# LED0805-8_Sch.net
KiCad netlist of a schematic drawn in Altium Designer
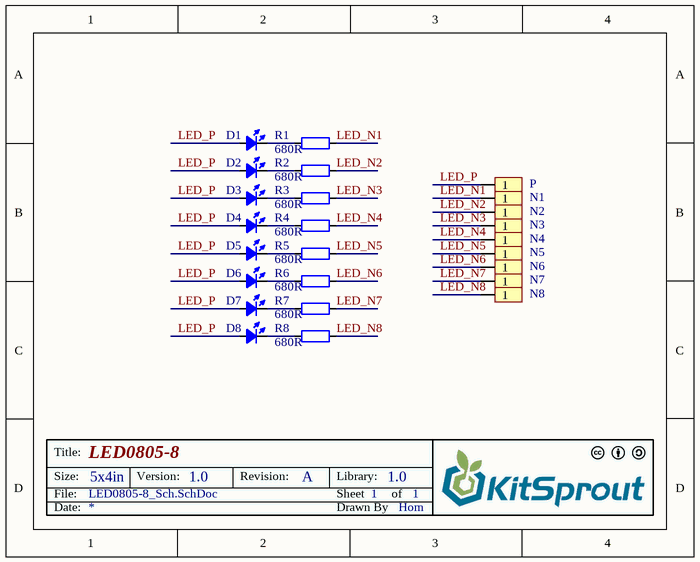
[diagram p0: LED0805-8_Sch.SchDoc]

(export (version "E")
  (design (tool "Eeschema 10.0.6"))
  (components
    (comp (ref "D1")
      (value "LED_0805")
      (footprint "PCB_ActiveLED:LED_0805_BLUE")
      (description "LED")
      (libsource (lib "SCH_Active") (part "LED_0805"))
    )
    (comp (ref "D2")
      (value "LED_0805")
      (footprint "PCB_ActiveLED:LED_0805_BLUE")
      (description "LED")
      (libsource (lib "SCH_Active") (part "LED_0805"))
    )
    (comp (ref "D3")
      (value "LED_0805")
      (footprint "PCB_ActiveLED:LED_0805_BLUE")
      (description "LED")
      (libsource (lib "SCH_Active") (part "LED_0805"))
    )
    (comp (ref "D4")
      (value "LED_0805")
      (footprint "PCB_ActiveLED:LED_0805_BLUE")
      (description "LED")
      (libsource (lib "SCH_Active") (part "LED_0805"))
    )
    (comp (ref "D5")
      (value "LED_0805")
      (footprint "PCB_ActiveLED:LED_0805_BLUE")
      (description "LED")
      (libsource (lib "SCH_Active") (part "LED_0805"))
    )
    (comp (ref "D6")
      (value "LED_0805")
      (footprint "PCB_ActiveLED:LED_0805_BLUE")
      (description "LED")
      (libsource (lib "SCH_Active") (part "LED_0805"))
    )
    (comp (ref "D7")
      (value "LED_0805")
      (footprint "PCB_ActiveLED:LED_0805_BLUE")
      (description "LED")
      (libsource (lib "SCH_Active") (part "LED_0805"))
    )
    (comp (ref "D8")
      (value "LED_0805")
      (footprint "PCB_ActiveLED:LED_0805_BLUE")
      (description "LED")
      (libsource (lib "SCH_Active") (part "LED_0805"))
    )
    (comp (ref "N1")
      (value "HDR-PAD_2.54")
      (footprint "PCB_ConnectorHDR:HDR-PAD_2.54")
      (description "Header")
      (libsource (lib "SCH_ConnectorHDR") (part "HDR-PAD_2.54"))
    )
    (comp (ref "N2")
      (value "HDR-PAD_2.54")
      (footprint "PCB_ConnectorHDR:HDR-PAD_2.54")
      (description "Header")
      (libsource (lib "SCH_ConnectorHDR") (part "HDR-PAD_2.54"))
    )
    (comp (ref "N3")
      (value "HDR-PAD_2.54")
      (footprint "PCB_ConnectorHDR:HDR-PAD_2.54")
      (description "Header")
      (libsource (lib "SCH_ConnectorHDR") (part "HDR-PAD_2.54"))
    )
    (comp (ref "N4")
      (value "HDR-PAD_2.54")
      (footprint "PCB_ConnectorHDR:HDR-PAD_2.54")
      (description "Header")
      (libsource (lib "SCH_ConnectorHDR") (part "HDR-PAD_2.54"))
    )
    (comp (ref "N5")
      (value "HDR-PAD_2.54")
      (footprint "PCB_ConnectorHDR:HDR-PAD_2.54")
      (description "Header")
      (libsource (lib "SCH_ConnectorHDR") (part "HDR-PAD_2.54"))
    )
    (comp (ref "N6")
      (value "HDR-PAD_2.54")
      (footprint "PCB_ConnectorHDR:HDR-PAD_2.54")
      (description "Header")
      (libsource (lib "SCH_ConnectorHDR") (part "HDR-PAD_2.54"))
    )
    (comp (ref "N7")
      (value "HDR-PAD_2.54")
      (footprint "PCB_ConnectorHDR:HDR-PAD_2.54")
      (description "Header")
      (libsource (lib "SCH_ConnectorHDR") (part "HDR-PAD_2.54"))
    )
    (comp (ref "N8")
      (value "HDR-PAD_2.54")
      (footprint "PCB_ConnectorHDR:HDR-PAD_2.54")
      (description "Header")
      (libsource (lib "SCH_ConnectorHDR") (part "HDR-PAD_2.54"))
    )
    (comp (ref "P")
      (value "HDR-PAD_2.54")
      (footprint "PCB_ConnectorHDR:HDR-PAD_2.54")
      (description "Header")
      (libsource (lib "SCH_ConnectorHDR") (part "HDR-PAD_2.54"))
    )
    (comp (ref "R1")
      (value "680R")
      (footprint "PCB_PassiveRes:RES_0805")
      (description "Resistor")
      (fields (field (name "Comment") "Res_0805"))
      (libsource (lib "SCH_Passive") (part "Res_0805"))
    )
    (comp (ref "R2")
      (value "680R")
      (footprint "PCB_PassiveRes:RES_0805")
      (description "Resistor")
      (fields (field (name "Comment") "Res_0805"))
      (libsource (lib "SCH_Passive") (part "Res_0805"))
    )
    (comp (ref "R3")
      (value "680R")
      (footprint "PCB_PassiveRes:RES_0805")
      (description "Resistor")
      (fields (field (name "Comment") "Res_0805"))
      (libsource (lib "SCH_Passive") (part "Res_0805"))
    )
    (comp (ref "R4")
      (value "680R")
      (footprint "PCB_PassiveRes:RES_0805")
      (description "Resistor")
      (fields (field (name "Comment") "Res_0805"))
      (libsource (lib "SCH_Passive") (part "Res_0805"))
    )
    (comp (ref "R5")
      (value "680R")
      (footprint "PCB_PassiveRes:RES_0805")
      (description "Resistor")
      (fields (field (name "Comment") "Res_0805"))
      (libsource (lib "SCH_Passive") (part "Res_0805"))
    )
    (comp (ref "R6")
      (value "680R")
      (footprint "PCB_PassiveRes:RES_0805")
      (description "Resistor")
      (fields (field (name "Comment") "Res_0805"))
      (libsource (lib "SCH_Passive") (part "Res_0805"))
    )
    (comp (ref "R7")
      (value "680R")
      (footprint "PCB_PassiveRes:RES_0805")
      (description "Resistor")
      (fields (field (name "Comment") "Res_0805"))
      (libsource (lib "SCH_Passive") (part "Res_0805"))
    )
    (comp (ref "R8")
      (value "680R")
      (footprint "PCB_PassiveRes:RES_0805")
      (description "Resistor")
      (fields (field (name "Comment") "Res_0805"))
      (libsource (lib "SCH_Passive") (part "Res_0805"))
    )
  )
  (nets
    (net (code "1") (name "/LED_N1") (class "Default")
      (node (ref "N1") (pin "1") (pinfunction "1_1") (pintype "passive"))
      (node (ref "R1") (pin "2") (pinfunction "2_2") (pintype "passive"))
    )
    (net (code "2") (name "/LED_N2") (class "Default")
      (node (ref "N2") (pin "1") (pinfunction "1_1") (pintype "passive"))
      (node (ref "R2") (pin "2") (pinfunction "2_2") (pintype "passive"))
    )
    (net (code "3") (name "/LED_N3") (class "Default")
      (node (ref "N3") (pin "1") (pinfunction "1_1") (pintype "passive"))
      (node (ref "R3") (pin "2") (pinfunction "2_2") (pintype "passive"))
    )
    (net (code "4") (name "/LED_N4") (class "Default")
      (node (ref "N4") (pin "1") (pinfunction "1_1") (pintype "passive"))
      (node (ref "R4") (pin "2") (pinfunction "2_2") (pintype "passive"))
    )
    (net (code "5") (name "/LED_N5") (class "Default")
      (node (ref "N5") (pin "1") (pinfunction "1_1") (pintype "passive"))
      (node (ref "R5") (pin "2") (pinfunction "2_2") (pintype "passive"))
    )
    (net (code "6") (name "/LED_N6") (class "Default")
      (node (ref "N6") (pin "1") (pinfunction "1_1") (pintype "passive"))
      (node (ref "R6") (pin "2") (pinfunction "2_2") (pintype "passive"))
    )
    (net (code "7") (name "/LED_N7") (class "Default")
      (node (ref "N7") (pin "1") (pinfunction "1_1") (pintype "passive"))
      (node (ref "R7") (pin "2") (pinfunction "2_2") (pintype "passive"))
    )
    (net (code "8") (name "/LED_N8") (class "Default")
      (node (ref "N8") (pin "1") (pinfunction "1_1") (pintype "passive"))
      (node (ref "R8") (pin "2") (pinfunction "2_2") (pintype "passive"))
    )
    (net (code "9") (name "/LED_P") (class "Default")
      (node (ref "D1") (pin "1") (pinfunction "A_1") (pintype "passive"))
      (node (ref "D2") (pin "1") (pinfunction "A_1") (pintype "passive"))
      (node (ref "D3") (pin "1") (pinfunction "A_1") (pintype "passive"))
      (node (ref "D4") (pin "1") (pinfunction "A_1") (pintype "passive"))
      (node (ref "D5") (pin "1") (pinfunction "A_1") (pintype "passive"))
      (node (ref "D6") (pin "1") (pinfunction "A_1") (pintype "passive"))
      (node (ref "D7") (pin "1") (pinfunction "A_1") (pintype "passive"))
      (node (ref "D8") (pin "1") (pinfunction "A_1") (pintype "passive"))
      (node (ref "P") (pin "1") (pinfunction "1_1") (pintype "passive"))
    )
    (net (code "10") (name "Net-(D1-K)") (class "Default")
      (node (ref "D1") (pin "2") (pinfunction "K_2") (pintype "passive"))
      (node (ref "R1") (pin "1") (pinfunction "1_1") (pintype "passive"))
    )
    (net (code "11") (name "Net-(D2-K)") (class "Default")
      (node (ref "D2") (pin "2") (pinfunction "K_2") (pintype "passive"))
      (node (ref "R2") (pin "1") (pinfunction "1_1") (pintype "passive"))
    )
    (net (code "12") (name "Net-(D3-K)") (class "Default")
      (node (ref "D3") (pin "2") (pinfunction "K_2") (pintype "passive"))
      (node (ref "R3") (pin "1") (pinfunction "1_1") (pintype "passive"))
    )
    (net (code "13") (name "Net-(D4-K)") (class "Default")
      (node (ref "D4") (pin "2") (pinfunction "K_2") (pintype "passive"))
      (node (ref "R4") (pin "1") (pinfunction "1_1") (pintype "passive"))
    )
    (net (code "14") (name "Net-(D5-K)") (class "Default")
      (node (ref "D5") (pin "2") (pinfunction "K_2") (pintype "passive"))
      (node (ref "R5") (pin "1") (pinfunction "1_1") (pintype "passive"))
    )
    (net (code "15") (name "Net-(D6-K)") (class "Default")
      (node (ref "D6") (pin "2") (pinfunction "K_2") (pintype "passive"))
      (node (ref "R6") (pin "1") (pinfunction "1_1") (pintype "passive"))
    )
    (net (code "16") (name "Net-(D7-K)") (class "Default")
      (node (ref "D7") (pin "2") (pinfunction "K_2") (pintype "passive"))
      (node (ref "R7") (pin "1") (pinfunction "1_1") (pintype "passive"))
    )
    (net (code "17") (name "Net-(D8-K)") (class "Default")
      (node (ref "D8") (pin "2") (pinfunction "K_2") (pintype "passive"))
      (node (ref "R8") (pin "1") (pinfunction "1_1") (pintype "passive"))
    )
  )
)
